# Wifi-ESP32.net
KiCad netlist of a schematic drawn in Altium Designer
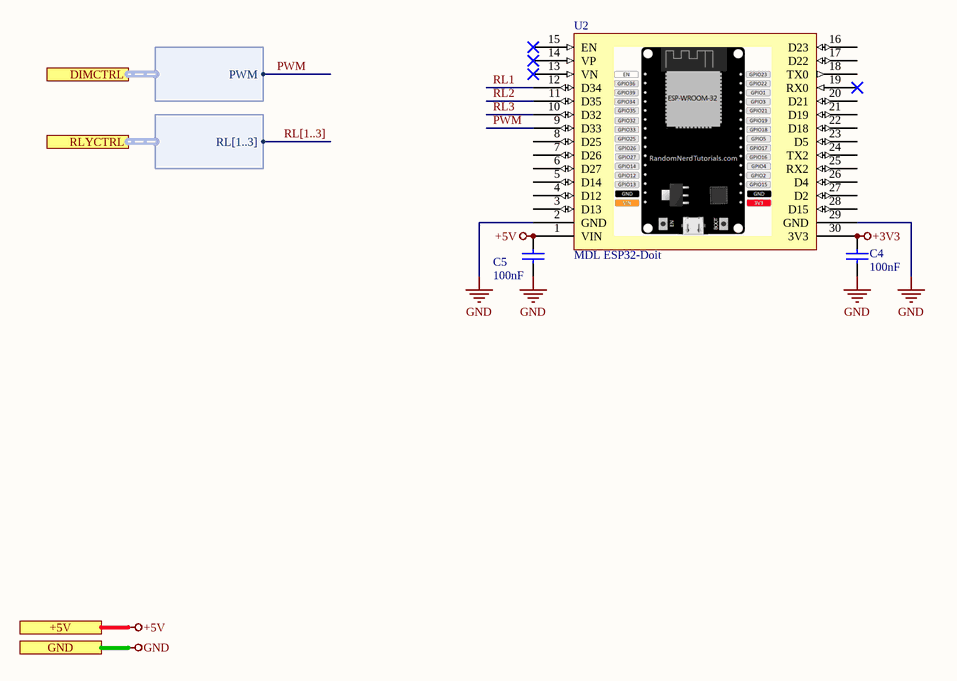
[diagram p0: Wifi-ESP32.SchDoc]

(export (version "E")
  (design (tool "Eeschema 10.0.6"))
  (components
    (comp (ref "C4")
      (value "100nF")
      (footprint "C-0805")
      (description "Capacitor")
      (fields (field (name "Comment") "104") (field (name "PUBLISHER") "Altium Limited"))
      (libsource (lib "Miscellaneous Devices") (part "Cap"))
    )
    (comp (ref "C5")
      (value "100nF")
      (footprint "C-0805")
      (description "Capacitor")
      (fields (field (name "Comment") "104") (field (name "PUBLISHER") "Altium Limited"))
      (libsource (lib "Miscellaneous Devices") (part "Cap"))
    )
    (comp (ref "U2")
      (value "MDL ESP32-Doit")
      (footprint "MDL-ESP32-DOIT")
      (description "ESP32 DEVKIT V1 DOIT")
      (libsource (lib "Dlib") (part "MDL ESP32-Doit"))
    )
  )
  (nets
    (net (code "3") (name "+3V3") (class "Default")
      (node (ref "C4") (pin "1") (pinfunction "1_1") (pintype "passive"))
      (node (ref "U2") (pin "30") (pinfunction "3V3_30") (pintype "power_in"))
    )
    (net (code "4") (name "+5V") (class "Default")
      (node (ref "C5") (pin "1") (pinfunction "1_1") (pintype "passive"))
      (node (ref "U2") (pin "1") (pinfunction "VIN_1") (pintype "power_in"))
    )
    (net (code "5") (name "/PWM") (class "Default")
      (node (ref "U2") (pin "9") (pinfunction "D33_9") (pintype "bidirectional"))
    )
    (net (code "6") (name "/RL1") (class "Default")
      (node (ref "U2") (pin "12") (pinfunction "D34_12") (pintype "bidirectional"))
    )
    (net (code "7") (name "/RL2") (class "Default")
      (node (ref "U2") (pin "11") (pinfunction "D35_11") (pintype "bidirectional"))
    )
    (net (code "8") (name "/RL3") (class "Default")
      (node (ref "U2") (pin "10") (pinfunction "D32_10") (pintype "bidirectional"))
    )
    (net (code "12") (name "GND") (class "Default")
      (node (ref "C4") (pin "2") (pinfunction "2_2") (pintype "passive"))
      (node (ref "C5") (pin "2") (pinfunction "2_2") (pintype "passive"))
      (node (ref "U2") (pin "2") (pinfunction "GND_2") (pintype "power_in"))
      (node (ref "U2") (pin "29") (pinfunction "GND_29") (pintype "power_in"))
    )
    (net (code "13") (name "unconnected-(U2-D2-Pad27)") (class "Default")
      (node (ref "U2") (pin "27") (pinfunction "D2_27") (pintype "bidirectional"))
    )
    (net (code "14") (name "unconnected-(U2-D4-Pad26)") (class "Default")
      (node (ref "U2") (pin "26") (pinfunction "D4_26") (pintype "bidirectional"))
    )
    (net (code "15") (name "unconnected-(U2-D5-Pad23)") (class "Default")
      (node (ref "U2") (pin "23") (pinfunction "D5_23") (pintype "bidirectional"))
    )
    (net (code "16") (name "unconnected-(U2-D12-Pad4)") (class "Default")
      (node (ref "U2") (pin "4") (pinfunction "D12_4") (pintype "bidirectional"))
    )
    (net (code "17") (name "unconnected-(U2-D13-Pad3)") (class "Default")
      (node (ref "U2") (pin "3") (pinfunction "D13_3") (pintype "bidirectional"))
    )
    (net (code "18") (name "unconnected-(U2-D14-Pad5)") (class "Default")
      (node (ref "U2") (pin "5") (pinfunction "D14_5") (pintype "bidirectional"))
    )
    (net (code "19") (name "unconnected-(U2-D15-Pad28)") (class "Default")
      (node (ref "U2") (pin "28") (pinfunction "D15_28") (pintype "bidirectional"))
    )
    (net (code "20") (name "unconnected-(U2-D18-Pad22)") (class "Default")
      (node (ref "U2") (pin "22") (pinfunction "D18_22") (pintype "bidirectional"))
    )
    (net (code "21") (name "unconnected-(U2-D19-Pad21)") (class "Default")
      (node (ref "U2") (pin "21") (pinfunction "D19_21") (pintype "bidirectional"))
    )
    (net (code "22") (name "unconnected-(U2-D21-Pad20)") (class "Default")
      (node (ref "U2") (pin "20") (pinfunction "D21_20") (pintype "bidirectional"))
    )
    (net (code "23") (name "unconnected-(U2-D22-Pad17)") (class "Default")
      (node (ref "U2") (pin "17") (pinfunction "D22_17") (pintype "bidirectional"))
    )
    (net (code "24") (name "unconnected-(U2-D23-Pad16)") (class "Default")
      (node (ref "U2") (pin "16") (pinfunction "D23_16") (pintype "bidirectional"))
    )
    (net (code "25") (name "unconnected-(U2-D25-Pad8)") (class "Default")
      (node (ref "U2") (pin "8") (pinfunction "D25_8") (pintype "bidirectional"))
    )
    (net (code "26") (name "unconnected-(U2-D26-Pad7)") (class "Default")
      (node (ref "U2") (pin "7") (pinfunction "D26_7") (pintype "bidirectional"))
    )
    (net (code "27") (name "unconnected-(U2-D27-Pad6)") (class "Default")
      (node (ref "U2") (pin "6") (pinfunction "D27_6") (pintype "bidirectional"))
    )
    (net (code "28") (name "unconnected-(U2-EN-Pad15)") (class "Default")
      (node (ref "U2") (pin "15") (pinfunction "EN_15") (pintype "input+no_connect"))
    )
    (net (code "29") (name "unconnected-(U2-RX0-Pad19)") (class "Default")
      (node (ref "U2") (pin "19") (pinfunction "RX0_19") (pintype "input+no_connect"))
    )
    (net (code "30") (name "unconnected-(U2-RX2-Pad25)") (class "Default")
      (node (ref "U2") (pin "25") (pinfunction "RX2_25") (pintype "bidirectional"))
    )
    (net (code "31") (name "unconnected-(U2-TX0-Pad18)") (class "Default")
      (node (ref "U2") (pin "18") (pinfunction "TX0_18") (pintype "output"))
    )
    (net (code "32") (name "unconnected-(U2-TX2-Pad24)") (class "Default")
      (node (ref "U2") (pin "24") (pinfunction "TX2_24") (pintype "bidirectional"))
    )
    (net (code "33") (name "unconnected-(U2-VN-Pad13)") (class "Default")
      (node (ref "U2") (pin "13") (pinfunction "VN_13") (pintype "input+no_connect"))
    )
    (net (code "34") (name "unconnected-(U2-VP-Pad14)") (class "Default")
      (node (ref "U2") (pin "14") (pinfunction "VP_14") (pintype "input+no_connect"))
    )
  )
)
